# power.net
KiCad netlist of a schematic drawn in Altium Designer
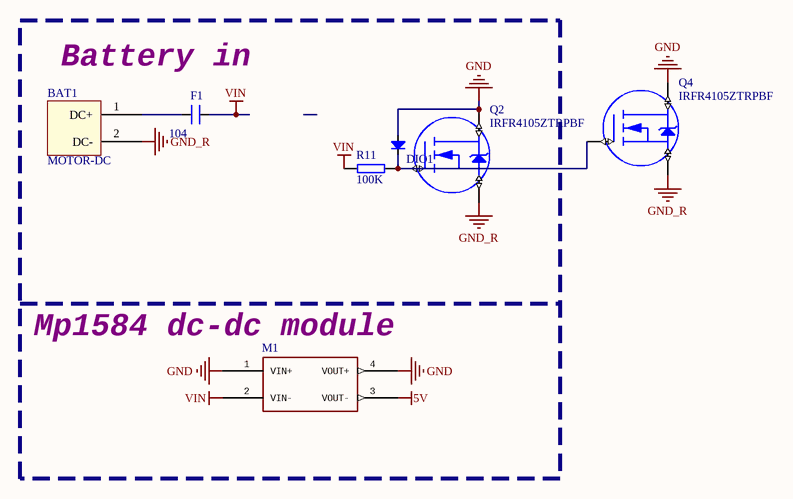
[diagram p0: power.SchDoc]

(export (version "E")
  (design (tool "Eeschema 10.0.6"))
  (components
    (comp (ref "BAT1")
      (value "MOTOR-DC")
      (footprint "CON2-5.08DC")
      (libsource (lib "RASHBERRY_EXTERN") (part "MOTOR-DC"))
    )
    (comp (ref "DIO1")
      (value "Diode SMD")
      (footprint "DIO-SMD-123")
      (description "Default Diode")
      (fields (field (name "PUBLISHER") "Altium Limited"))
      (libsource (lib "My Library") (part "Diode SMD"))
    )
    (comp (ref "F1")
      (value "104")
      (footprint "CN2")
      (description "Cap np 104 => 105pF")
      (libsource (lib "My Library") (part "CN2"))
    )
    (comp (ref "M1")
      (value "MP1584-dc-brick-pcb Step down Input: 4.5V - 28V Ouput 0.8V - 25V max. 3A Cheap on ebay")
      (footprint "MP1584 MODULE")
      (libsource (lib "MP1584-dc-brick") (part "MP1584"))
    )
    (comp (ref "Q2")
      (value "IRFR4105ZTRPBF")
      (footprint "TO252-3:TO252-3")
      (description "RoHS Compliant ¦ Industry-leading quality ¦ Fast Switching ¦ 175C Operating Temperature")
      (fields
        (field (name "DIGI-KEY_PART_NUMBER") "IRFR4105ZTRPBFCT-ND")
        (field (name "MF") "Infineon Technologies")
      )
      (libsource (lib "IRFR4105ZTRPBF") (part "IRFR4105ZTRPBF"))
    )
    (comp (ref "Q4")
      (value "IRFR4105ZTRPBF")
      (footprint "TO252-3:TO252-3")
      (description "RoHS Compliant ¦ Industry-leading quality ¦ Fast Switching ¦ 175C Operating Temperature")
      (fields
        (field (name "DIGI-KEY_PART_NUMBER") "IRFR4105ZTRPBFCT-ND")
        (field (name "MF") "Infineon Technologies")
      )
      (libsource (lib "IRFR4105ZTRPBF") (part "IRFR4105ZTRPBF"))
    )
    (comp (ref "R11")
      (value "100K")
      (footprint "SMT0603")
      (description "RES SM 0603 100K")
      (fields (field (name "Comment") "Resistor"))
      (libsource (lib "electronpowered") (part "RES-SM-0603-100K"))
    )
  )
  (nets
    (net (code "1") (name "5V") (class "Default")
      (node (ref "M1") (pin "3") (pinfunction "VOUT-_3") (pintype "output"))
    )
    (net (code "2") (name "GND") (class "Default")
      (node (ref "DIO1") (pin "1") (pinfunction "A_1") (pintype "passive"))
      (node (ref "M1") (pin "1") (pinfunction "VIN+_1") (pintype "passive"))
      (node (ref "M1") (pin "4") (pinfunction "VOUT+_4") (pintype "output"))
      (node (ref "Q2") (pin "2") (pinfunction "D@1_2") (pintype "bidirectional"))
      (node (ref "Q4") (pin "2") (pinfunction "D@1_2") (pintype "bidirectional"))
    )
    (net (code "3") (name "GND_R") (class "Default")
      (node (ref "BAT1") (pin "2") (pinfunction "DC-_2") (pintype "passive"))
      (node (ref "Q2") (pin "3") (pinfunction "S_3") (pintype "bidirectional"))
      (node (ref "Q4") (pin "3") (pinfunction "S_3") (pintype "bidirectional"))
    )
    (net (code "4") (name "Net-(BAT1-DC+)") (class "Default")
      (node (ref "BAT1") (pin "1") (pinfunction "DC+_1") (pintype "passive"))
      (node (ref "F1") (pin "1") (pinfunction "1_1") (pintype "passive"))
    )
    (net (code "5") (name "Net-(DIO1-K)") (class "Default")
      (node (ref "DIO1") (pin "2") (pinfunction "K_2") (pintype "passive"))
      (node (ref "Q2") (pin "1") (pinfunction "G_1") (pintype "bidirectional"))
      (node (ref "Q4") (pin "1") (pinfunction "G_1") (pintype "bidirectional"))
      (node (ref "R11") (pin "1") (pinfunction "1_1") (pintype "passive"))
    )
    (net (code "6") (name "VIN") (class "Default")
      (node (ref "F1") (pin "2") (pinfunction "2_2") (pintype "passive"))
      (node (ref "M1") (pin "2") (pinfunction "VIN-_2") (pintype "passive"))
      (node (ref "R11") (pin "2") (pinfunction "2_2") (pintype "passive"))
    )
    (net (code "7") (name "unconnected-(Q2-D@2-PadPAD)") (class "Default")
      (node (ref "Q2") (pin "PAD") (pinfunction "D@2_PAD") (pintype "bidirectional"))
    )
    (net (code "8") (name "unconnected-(Q4-D@2-PadPAD)") (class "Default")
      (node (ref "Q4") (pin "PAD") (pinfunction "D@2_PAD") (pintype "bidirectional"))
    )
  )
)
